# MCU.net
KiCad netlist of a schematic drawn in Altium Designer
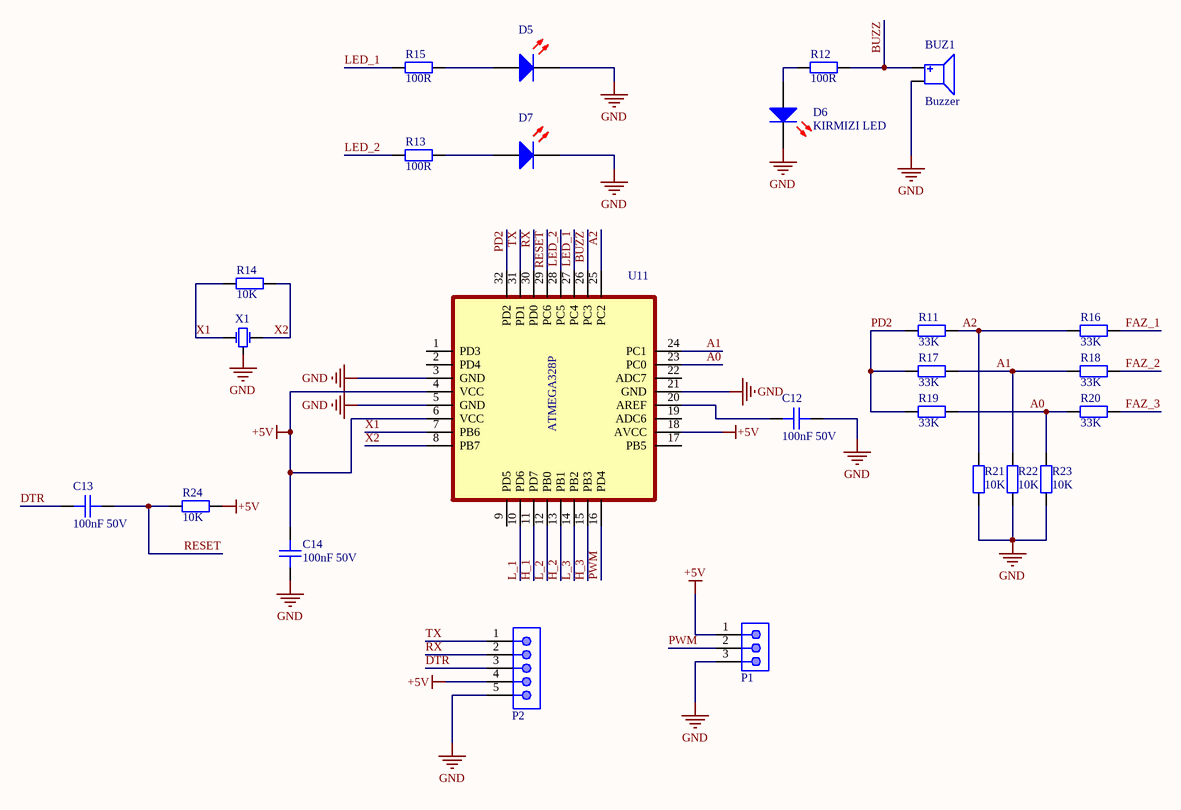
[diagram p0: MCU.SchDoc]

(export (version "E")
  (design (tool "Eeschema 10.0.6"))
  (components
    (comp (ref "BUZ1")
      (value "BUZZER MAGN 3.6V 7.5X7.5MM SMD")
      (footprint "BUZ: CMT-7525")
      (fields (field (name "DEGER") "Buzzer"))
      (libsource (lib "PROJE") (part "Buzzer(CMT-7525-80-SMT-TR)"))
    )
    (comp (ref "C12")
      (value "CAP CER 0.1UF 50V X7R 0805")
      (footprint "CAP 0805/2012")
      (description "0.1µF ±10% 50V Ceramic Capacitor X7R 0805 (2012 Metric)")
      (fields (field (name "DEGER") "100nF 50V"))
      (libsource (lib "PROJE") (part "100nF 50V 0805"))
    )
    (comp (ref "C13")
      (value "CAP CER 0.1UF 50V X7R 0805")
      (footprint "CAP 0805/2012")
      (description "0.1µF ±10% 50V Ceramic Capacitor X7R 0805 (2012 Metric)")
      (fields (field (name "DEGER") "100nF 50V"))
      (libsource (lib "PROJE") (part "100nF 50V 0805"))
    )
    (comp (ref "C14")
      (value "CAP CER 0.1UF 50V X7R 0805")
      (footprint "CAP 0805/2012")
      (description "0.1µF ±10% 50V Ceramic Capacitor X7R 0805 (2012 Metric)")
      (fields (field (name "DEGER") "100nF 50V"))
      (libsource (lib "PROJE") (part "100nF 50V 0805"))
    )
    (comp (ref "D5")
      (value "Red 645nm LED Indication - Discrete 1.8V 0805")
      (footprint "SMD: LED 0805/2012 RED")
      (description "LED RED DIFFUSED 0805 SMD")
      (libsource (lib "PROJE") (part "LED_Kırmızı"))
    )
    (comp (ref "D6")
      (value "Red 645nm LED Indication - Discrete 1.8V 0805")
      (footprint "SMD: LED 0805/2012 RED")
      (description "LED RED DIFFUSED 0805 SMD")
      (fields (field (name "DEGER") "KIRMIZI LED"))
      (libsource (lib "PROJE") (part "LED_Kırmızı"))
    )
    (comp (ref "D7")
      (value "Red 645nm LED Indication - Discrete 1.8V 0805")
      (footprint "SMD: LED 0805/2012 RED")
      (description "LED RED DIFFUSED 0805 SMD")
      (libsource (lib "PROJE") (part "LED_Kırmızı"))
    )
    (comp (ref "P1")
      (value "WR-PHD 2.54 mm Angled Socket Header")
      (footprint "PWM_CONN")
      (libsource (lib "PROJE") (part "HDR(1X3)"))
    )
    (comp (ref "P2")
      (value "WR-PHD 2.54 mm Angled Socket Header")
      (footprint "TTL_CONN_5")
      (libsource (lib "PROJE") (part "HDR(1X5)"))
    )
    (comp (ref "R11")
      (value "RES SMD 33K OHM 1% 1/8W 0805")
      (footprint "RES_0805")
      (description "33 kOhms ±1% 0.125W, 1/8W Chip Resistor 0805 (2012 Metric) Moisture Resistant Thick Film")
      (fields (field (name "DEGER") "33K"))
      (libsource (lib "PROJE") (part "33K 0805"))
    )
    (comp (ref "R12")
      (value "RES SMD 100 OHM 1% 1/8W 0805")
      (footprint "RES_0805")
      (description "100 Ohms ±1% 0.125W, 1/8W Chip Resistor 0805 (2012 Metric) Moisture Resistant Thick Film")
      (fields (field (name "DEGER") "100R"))
      (libsource (lib "PROJE") (part "100R 0805"))
    )
    (comp (ref "R13")
      (value "RES SMD 100 OHM 1% 1/8W 0805")
      (footprint "RES_0805")
      (description "100 Ohms ±1% 0.125W, 1/8W Chip Resistor 0805 (2012 Metric) Moisture Resistant Thick Film")
      (fields (field (name "DEGER") "100R"))
      (libsource (lib "PROJE") (part "100R 0805"))
    )
    (comp (ref "R14")
      (value "RES SMD 10K OHM 1% 1/8W 0805")
      (footprint "RES_0805")
      (description "10 kOhms ±1% 0.125W, 1/8W Chip Resistor 0805 (2012 Metric) Moisture Resistant Thick Film")
      (fields (field (name "DEGER") "10K"))
      (libsource (lib "") (part "10K 0805_1"))
    )
    (comp (ref "R15")
      (value "RES SMD 100 OHM 1% 1/8W 0805")
      (footprint "RES_0805")
      (description "100 Ohms ±1% 0.125W, 1/8W Chip Resistor 0805 (2012 Metric) Moisture Resistant Thick Film")
      (fields (field (name "DEGER") "100R"))
      (libsource (lib "PROJE") (part "100R 0805"))
    )
    (comp (ref "R16")
      (value "RES SMD 33K OHM 1% 1/8W 0805")
      (footprint "RES_0805")
      (description "33 kOhms ±1% 0.125W, 1/8W Chip Resistor 0805 (2012 Metric) Moisture Resistant Thick Film")
      (fields (field (name "DEGER") "33K"))
      (libsource (lib "PROJE") (part "33K 0805"))
    )
    (comp (ref "R17")
      (value "RES SMD 33K OHM 1% 1/8W 0805")
      (footprint "RES_0805")
      (description "33 kOhms ±1% 0.125W, 1/8W Chip Resistor 0805 (2012 Metric) Moisture Resistant Thick Film")
      (fields (field (name "DEGER") "33K"))
      (libsource (lib "PROJE") (part "33K 0805"))
    )
    (comp (ref "R18")
      (value "RES SMD 33K OHM 1% 1/8W 0805")
      (footprint "RES_0805")
      (description "33 kOhms ±1% 0.125W, 1/8W Chip Resistor 0805 (2012 Metric) Moisture Resistant Thick Film")
      (fields (field (name "DEGER") "33K"))
      (libsource (lib "PROJE") (part "33K 0805"))
    )
    (comp (ref "R19")
      (value "RES SMD 33K OHM 1% 1/8W 0805")
      (footprint "RES_0805")
      (description "33 kOhms ±1% 0.125W, 1/8W Chip Resistor 0805 (2012 Metric) Moisture Resistant Thick Film")
      (fields (field (name "DEGER") "33K"))
      (libsource (lib "PROJE") (part "33K 0805"))
    )
    (comp (ref "R20")
      (value "RES SMD 33K OHM 1% 1/8W 0805")
      (footprint "RES_0805")
      (description "33 kOhms ±1% 0.125W, 1/8W Chip Resistor 0805 (2012 Metric) Moisture Resistant Thick Film")
      (fields (field (name "DEGER") "33K"))
      (libsource (lib "PROJE") (part "33K 0805"))
    )
    (comp (ref "R21")
      (value "RES SMD 10K OHM 1% 1/8W 0805")
      (footprint "RES_0805")
      (description "10 kOhms ±1% 0.125W, 1/8W Chip Resistor 0805 (2012 Metric) Moisture Resistant Thick Film")
      (fields (field (name "DEGER") "10K"))
      (libsource (lib "PROJE") (part "10K 0805"))
    )
    (comp (ref "R22")
      (value "RES SMD 10K OHM 1% 1/8W 0805")
      (footprint "RES_0805")
      (description "10 kOhms ±1% 0.125W, 1/8W Chip Resistor 0805 (2012 Metric) Moisture Resistant Thick Film")
      (fields (field (name "DEGER") "10K"))
      (libsource (lib "PROJE") (part "10K 0805"))
    )
    (comp (ref "R23")
      (value "RES SMD 10K OHM 1% 1/8W 0805")
      (footprint "RES_0805")
      (description "10 kOhms ±1% 0.125W, 1/8W Chip Resistor 0805 (2012 Metric) Moisture Resistant Thick Film")
      (fields (field (name "DEGER") "10K"))
      (libsource (lib "PROJE") (part "10K 0805"))
    )
    (comp (ref "R24")
      (value "RES SMD 10K OHM 1% 1/8W 0805")
      (footprint "RES_0805")
      (description "10 kOhms ±1% 0.125W, 1/8W Chip Resistor 0805 (2012 Metric) Moisture Resistant Thick Film")
      (fields (field (name "DEGER") "10K"))
      (libsource (lib "") (part "10K 0805_1"))
    )
    (comp (ref "U11")
      (value "IC MCU 8BIT 32KB FLASH 32TQFP")
      (footprint "TQFP32")
      (description "AVR AVR® ATmega Microcontroller IC 8-Bit 20MHz 32KB (16K x 16) FLASH 32-TQFP (7x7)")
      (fields (field (name "DEGER") "ATMEGA328P"))
      (libsource (lib "PROJE") (part "ATMEGA328P"))
    )
    (comp (ref "X1")
      (value "CERAMIC RES 16.0000MHZ 15PF SMD")
      (footprint "CRYSTAL_16MHZ(CTSE16)")
      (description "16MHz Ceramic Resonator Built in Capacitor 15pF ±0.3%  -20°C ~ 80°C Surface Mount")
      (libsource (lib "PROJE") (part "CRYSTAL 16.0000MHZ(CSTCE16M0V53-R0)"))
    )
  )
  (nets
    (net (code "1") (name "+5V") (class "Default")
      (node (ref "C14") (pin "1") (pinfunction "1_1") (pintype "passive"))
      (node (ref "P1") (pin "1") (pinfunction "1_1") (pintype "passive"))
      (node (ref "P2") (pin "4") (pinfunction "4_4") (pintype "passive"))
      (node (ref "R24") (pin "2") (pinfunction "2_2") (pintype "passive"))
      (node (ref "U11") (pin "18") (pinfunction "AVCC_18") (pintype "passive"))
      (node (ref "U11") (pin "4") (pinfunction "VCC_4") (pintype "passive"))
      (node (ref "U11") (pin "6") (pinfunction "VCC_6") (pintype "passive"))
    )
    (net (code "2") (name "/A0") (class "Default")
      (node (ref "R19") (pin "2") (pinfunction "2_2") (pintype "passive"))
      (node (ref "R20") (pin "1") (pinfunction "1_1") (pintype "passive"))
      (node (ref "R23") (pin "2") (pinfunction "2_2") (pintype "passive"))
      (node (ref "U11") (pin "23") (pinfunction "PC0_23") (pintype "passive"))
    )
    (net (code "3") (name "/A1") (class "Default")
      (node (ref "R17") (pin "2") (pinfunction "2_2") (pintype "passive"))
      (node (ref "R18") (pin "1") (pinfunction "1_1") (pintype "passive"))
      (node (ref "R22") (pin "2") (pinfunction "2_2") (pintype "passive"))
      (node (ref "U11") (pin "24") (pinfunction "PC1_24") (pintype "passive"))
    )
    (net (code "4") (name "/A2") (class "Default")
      (node (ref "R11") (pin "2") (pinfunction "2_2") (pintype "passive"))
      (node (ref "R16") (pin "1") (pinfunction "1_1") (pintype "passive"))
      (node (ref "R21") (pin "2") (pinfunction "2_2") (pintype "passive"))
      (node (ref "U11") (pin "25") (pinfunction "PC2_25") (pintype "passive"))
    )
    (net (code "5") (name "/BUZZ") (class "Default")
      (node (ref "BUZ1") (pin "1") (pinfunction "Positive_1") (pintype "passive"))
      (node (ref "R12") (pin "2") (pinfunction "2_2") (pintype "passive"))
      (node (ref "U11") (pin "26") (pinfunction "PC3_26") (pintype "passive"))
    )
    (net (code "6") (name "/DTR") (class "Default")
      (node (ref "C13") (pin "1") (pinfunction "1_1") (pintype "passive"))
      (node (ref "P2") (pin "3") (pinfunction "3_3") (pintype "passive"))
    )
    (net (code "7") (name "/FAZ_1") (class "Default")
      (node (ref "R16") (pin "2") (pinfunction "2_2") (pintype "passive"))
    )
    (net (code "8") (name "/FAZ_2") (class "Default")
      (node (ref "R18") (pin "2") (pinfunction "2_2") (pintype "passive"))
    )
    (net (code "9") (name "/FAZ_3") (class "Default")
      (node (ref "R20") (pin "2") (pinfunction "2_2") (pintype "passive"))
    )
    (net (code "10") (name "/H_1") (class "Default")
      (node (ref "U11") (pin "11") (pinfunction "PD7_11") (pintype "passive"))
    )
    (net (code "11") (name "/H_2") (class "Default")
      (node (ref "U11") (pin "13") (pinfunction "PB1_13") (pintype "passive"))
    )
    (net (code "12") (name "/H_3") (class "Default")
      (node (ref "U11") (pin "15") (pinfunction "PB3_15") (pintype "passive"))
    )
    (net (code "13") (name "/LED_1") (class "Default")
      (node (ref "R15") (pin "1") (pinfunction "1_1") (pintype "passive"))
      (node (ref "U11") (pin "27") (pinfunction "PC4_27") (pintype "passive"))
    )
    (net (code "14") (name "/LED_2") (class "Default")
      (node (ref "R13") (pin "1") (pinfunction "1_1") (pintype "passive"))
      (node (ref "U11") (pin "28") (pinfunction "PC5_28") (pintype "passive"))
    )
    (net (code "15") (name "/L_1") (class "Default")
      (node (ref "U11") (pin "10") (pinfunction "PD6_10") (pintype "passive"))
    )
    (net (code "16") (name "/L_2") (class "Default")
      (node (ref "U11") (pin "12") (pinfunction "PB0_12") (pintype "passive"))
    )
    (net (code "17") (name "/L_3") (class "Default")
      (node (ref "U11") (pin "14") (pinfunction "PB2_14") (pintype "passive"))
    )
    (net (code "18") (name "/PD2") (class "Default")
      (node (ref "R11") (pin "1") (pinfunction "1_1") (pintype "passive"))
      (node (ref "R17") (pin "1") (pinfunction "1_1") (pintype "passive"))
      (node (ref "R19") (pin "1") (pinfunction "1_1") (pintype "passive"))
      (node (ref "U11") (pin "32") (pinfunction "PD2_32") (pintype "passive"))
    )
    (net (code "19") (name "/PWM") (class "Default")
      (node (ref "P1") (pin "2") (pinfunction "2_2") (pintype "passive"))
      (node (ref "U11") (pin "16") (pinfunction "PD4_16") (pintype "passive"))
    )
    (net (code "20") (name "/RESET") (class "Default")
      (node (ref "C13") (pin "2") (pinfunction "2_2") (pintype "passive"))
      (node (ref "R24") (pin "1") (pinfunction "1_1") (pintype "passive"))
      (node (ref "U11") (pin "29") (pinfunction "PC6_29") (pintype "passive"))
    )
    (net (code "21") (name "/RX") (class "Default")
      (node (ref "P2") (pin "2") (pinfunction "2_2") (pintype "passive"))
      (node (ref "U11") (pin "30") (pinfunction "PD0_30") (pintype "passive"))
    )
    (net (code "22") (name "/TX") (class "Default")
      (node (ref "P2") (pin "1") (pinfunction "1_1") (pintype "passive"))
      (node (ref "U11") (pin "31") (pinfunction "PD1_31") (pintype "passive"))
    )
    (net (code "23") (name "/X1") (class "Default")
      (node (ref "R14") (pin "1") (pinfunction "1_1") (pintype "passive"))
      (node (ref "U11") (pin "7") (pinfunction "PB6_7") (pintype "passive"))
      (node (ref "X1") (pin "1") (pinfunction "OSC1_1") (pintype "passive"))
    )
    (net (code "24") (name "/X2") (class "Default")
      (node (ref "R14") (pin "2") (pinfunction "2_2") (pintype "passive"))
      (node (ref "U11") (pin "8") (pinfunction "PB7_8") (pintype "passive"))
      (node (ref "X1") (pin "3") (pinfunction "OSC2_3") (pintype "passive"))
    )
    (net (code "25") (name "GND") (class "Default")
      (node (ref "BUZ1") (pin "2") (pinfunction "Negative_2") (pintype "passive"))
      (node (ref "C12") (pin "2") (pinfunction "2_2") (pintype "passive"))
      (node (ref "C14") (pin "2") (pinfunction "2_2") (pintype "passive"))
      (node (ref "D5") (pin "2") (pinfunction "K_2") (pintype "passive"))
      (node (ref "D6") (pin "2") (pinfunction "K_2") (pintype "passive"))
      (node (ref "D7") (pin "2") (pinfunction "K_2") (pintype "passive"))
      (node (ref "P1") (pin "3") (pinfunction "3_3") (pintype "passive"))
      (node (ref "P2") (pin "5") (pinfunction "5_5") (pintype "passive"))
      (node (ref "R21") (pin "1") (pinfunction "1_1") (pintype "passive"))
      (node (ref "R22") (pin "1") (pinfunction "1_1") (pintype "passive"))
      (node (ref "R23") (pin "1") (pinfunction "1_1") (pintype "passive"))
      (node (ref "U11") (pin "21") (pinfunction "GND_21") (pintype "passive"))
      (node (ref "U11") (pin "3") (pinfunction "GND_3") (pintype "passive"))
      (node (ref "U11") (pin "5") (pinfunction "GND_5") (pintype "passive"))
      (node (ref "X1") (pin "2") (pinfunction "GND_2") (pintype "passive"))
    )
    (net (code "26") (name "Net-(D5-A)") (class "Default")
      (node (ref "D5") (pin "1") (pinfunction "A_1") (pintype "passive"))
      (node (ref "R15") (pin "2") (pinfunction "2_2") (pintype "passive"))
    )
    (net (code "27") (name "Net-(D6-A)") (class "Default")
      (node (ref "D6") (pin "1") (pinfunction "A_1") (pintype "passive"))
      (node (ref "R12") (pin "1") (pinfunction "1_1") (pintype "passive"))
    )
    (net (code "28") (name "Net-(D7-A)") (class "Default")
      (node (ref "D7") (pin "1") (pinfunction "A_1") (pintype "passive"))
      (node (ref "R13") (pin "2") (pinfunction "2_2") (pintype "passive"))
    )
    (net (code "29") (name "Net-(U11-AREF)") (class "Default")
      (node (ref "C12") (pin "1") (pinfunction "1_1") (pintype "passive"))
      (node (ref "U11") (pin "20") (pinfunction "AREF_20") (pintype "passive"))
    )
    (net (code "30") (name "unconnected-(U11-ADC6-Pad19)") (class "Default")
      (node (ref "U11") (pin "19") (pinfunction "ADC6_19") (pintype "passive"))
    )
    (net (code "31") (name "unconnected-(U11-ADC7-Pad22)") (class "Default")
      (node (ref "U11") (pin "22") (pinfunction "ADC7_22") (pintype "passive"))
    )
    (net (code "32") (name "unconnected-(U11-PB5-Pad17)") (class "Default")
      (node (ref "U11") (pin "17") (pinfunction "PB5_17") (pintype "passive"))
    )
    (net (code "33") (name "unconnected-(U11-PD3-Pad1)") (class "Default")
      (node (ref "U11") (pin "1") (pinfunction "PD3_1") (pintype "passive"))
    )
    (net (code "34") (name "unconnected-(U11-PD4-Pad2)") (class "Default")
      (node (ref "U11") (pin "2") (pinfunction "PD4_2") (pintype "passive"))
    )
    (net (code "35") (name "unconnected-(U11-PD5-Pad9)") (class "Default")
      (node (ref "U11") (pin "9") (pinfunction "PD5_9") (pintype "passive"))
    )
  )
)
